# CH32L103G8R6-R0.net
KiCad netlist of a schematic drawn in Altium Designer
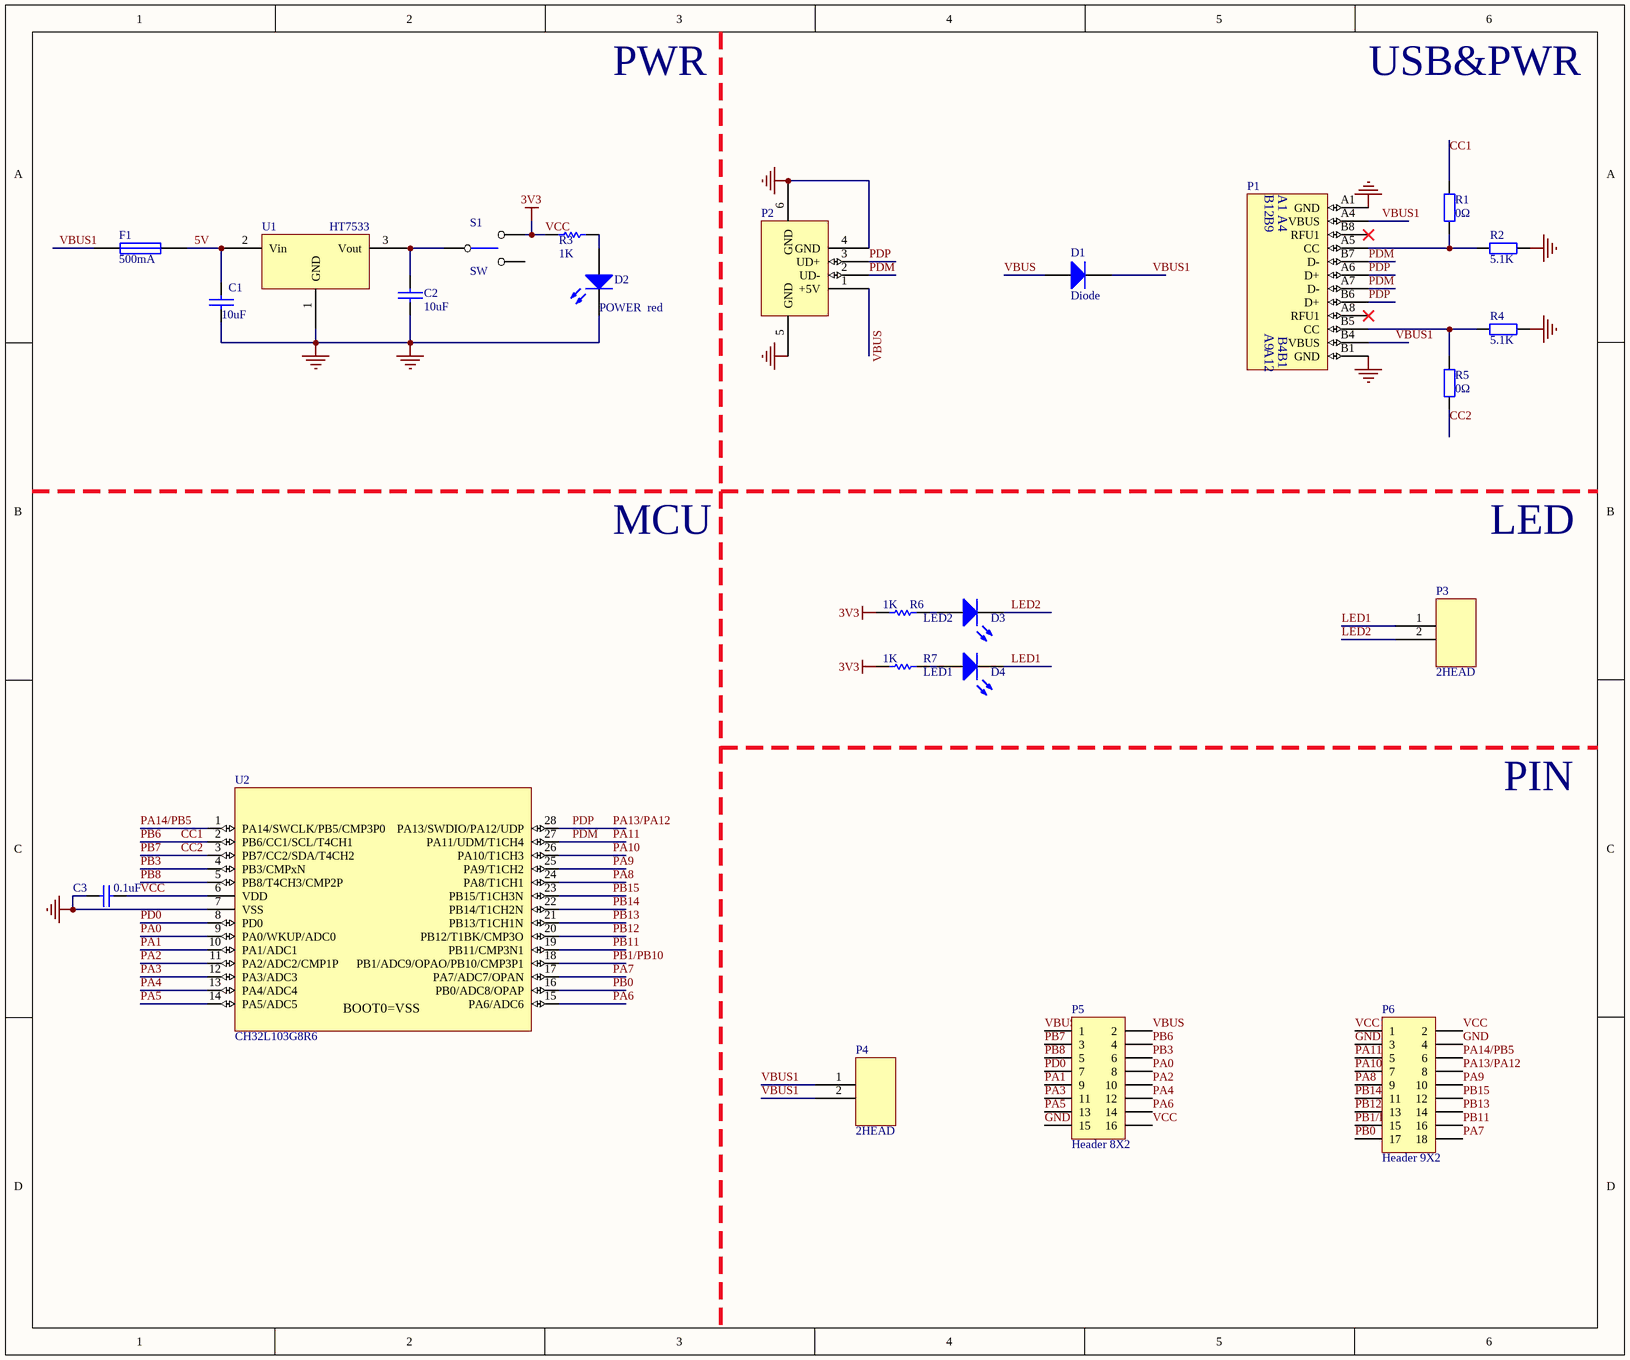
[diagram p0: CH32L103G8R6-R0.SchDoc]

(export (version "E")
  (design (tool "Eeschema 10.0.6"))
  (components
    (comp (ref "C1")
      (value "10uF")
      (footprint "0603_C")
      (description "Capacitor")
      (libsource (lib "*") (part "CAP"))
    )
    (comp (ref "C2")
      (value "10uF")
      (footprint "0603_C")
      (description "Capacitor")
      (libsource (lib "*") (part "CAP"))
    )
    (comp (ref "C3")
      (value "0.1uF")
      (footprint "0603_C")
      (description "Capacitor")
      (fields (field (name "PUBLISHER") "Altium Limited"))
      (libsource (lib "*") (part "Cap"))
    )
    (comp (ref "D1")
      (value "Diode")
      (footprint "SOD-123")
      (description "Default Diode")
      (fields (field (name "PUBLISHER") "Altium Limited"))
      (libsource (lib "Miscellaneous Devices") (part "Diode"))
    )
    (comp (ref "D2")
      (value "POWER  red")
      (footprint "0603+")
      (description "Typical INFRARED GaAs LED")
      (fields (field (name "PUBLISHER") "Altium Limited"))
      (libsource (lib "*") (part "LED0"))
    )
    (comp (ref "D3")
      (value "LED2")
      (footprint "0603+")
      (description "Typical INFRARED GaAs LED")
      (fields (field (name "PUBLISHER") "Altium Limited"))
      (libsource (lib "*") (part "LED0"))
    )
    (comp (ref "D4")
      (value "LED1")
      (footprint "0603+")
      (description "Typical INFRARED GaAs LED")
      (fields (field (name "PUBLISHER") "Altium Limited"))
      (libsource (lib "*") (part "LED0"))
    )
    (comp (ref "F1")
      (value "500mA")
      (footprint "0603")
      (description "Fuse")
      (libsource (lib "*") (part "FUSE1"))
    )
    (comp (ref "P1")
      (value "TYPE-C")
      (footprint "TYPE-C-Receptacle-2.0")
      (libsource (lib "*") (part "TYPE-C1"))
    )
    (comp (ref "P2")
      (value "USB_A")
      (footprint "USBAF")
      (description "USB Port")
      (libsource (lib "*") (part "USB"))
    )
    (comp (ref "P3") (value "2HEAD") (footprint "SIP2-2.54mm") (libsource (lib "*") (part "2HEAD")))
    (comp (ref "P4") (value "2HEAD") (footprint "SIP2-2.54mm") (libsource (lib "*") (part "2HEAD")))
    (comp (ref "P5")
      (value "Header 8X2")
      (footprint "HDR2X8")
      (description "Header, 8-Pin, Dual row")
      (fields (field (name "PUBLISHER") "Altium Limited"))
      (libsource (lib "Miscellaneous Connectors") (part "Header 8X2"))
    )
    (comp (ref "P6")
      (value "Header 9X2")
      (footprint "HDR2X9")
      (description "Header, 9-Pin, Dual row")
      (fields (field (name "PUBLISHER") "Altium Limited"))
      (libsource (lib "Miscellaneous Connectors") (part "Header 9X2"))
    )
    (comp (ref "R1")
      (value "0Ω")
      (footprint "0603")
      (description "Resistor")
      (libsource (lib "Miscellaneous Devices") (part "Res2"))
    )
    (comp (ref "R2")
      (value "5.1K")
      (footprint "0603")
      (description "Resistor")
      (libsource (lib "") (part "Res2_1"))
    )
    (comp (ref "R3")
      (value "1K")
      (footprint "0603")
      (description "Semiconductor Resistor")
      (libsource (lib "*") (part "Res Semi"))
    )
    (comp (ref "R4")
      (value "5.1K")
      (footprint "0603")
      (description "Resistor")
      (libsource (lib "") (part "Res2_1"))
    )
    (comp (ref "R5")
      (value "0Ω")
      (footprint "0603")
      (description "Resistor")
      (libsource (lib "Miscellaneous Devices") (part "Res2"))
    )
    (comp (ref "R6")
      (value "1K")
      (footprint "0603")
      (description "Semiconductor Resistor")
      (libsource (lib "*") (part "Res Semi"))
    )
    (comp (ref "R7")
      (value "1K")
      (footprint "0603")
      (description "Semiconductor Resistor")
      (libsource (lib "*") (part "Res Semi"))
    )
    (comp (ref "S1") (value "SW") (footprint "SW1") (libsource (lib "*") (part "SW")))
    (comp (ref "U1")
      (value "HT7533")
      (footprint "SOT-89")
      (libsource (lib "wch_sch_others") (part "1117-3.3V"))
    )
    (comp (ref "U2")
      (value "CH32L103G8R6")
      (footprint "QSOP28")
      (description "RISC-V LMD-MCU, 96MHz, USB, Type-C, CAN, OPA, lower power")
      (libsource (lib "DHXXXSCH") (part "CH32L103G8R6"))
    )
  )
  (nets
    (net (code "1") (name "/5V") (class "Default")
      (node (ref "C1") (pin "1") (pinfunction "1_1") (pintype "passive"))
      (node (ref "F1") (pin "2") (pinfunction "2_2") (pintype "passive"))
      (node (ref "U1") (pin "2") (pinfunction "Vin_2") (pintype "passive"))
    )
    (net (code "3") (name "/CC1") (class "Default")
      (node (ref "P5") (pin "4") (pinfunction "4_4") (pintype "passive"))
      (node (ref "R1") (pin "2") (pinfunction "2_2") (pintype "passive"))
      (node (ref "U2") (pin "2") (pinfunction "PB6/CC1/SCL/T4CH1_2") (pintype "bidirectional"))
    )
    (net (code "4") (name "/CC2") (class "Default")
      (node (ref "P5") (pin "3") (pinfunction "3_3") (pintype "passive"))
      (node (ref "R5") (pin "1") (pinfunction "1_1") (pintype "passive"))
      (node (ref "U2") (pin "3") (pinfunction "PB7/CC2/SDA/T4CH2_3") (pintype "bidirectional"))
    )
    (net (code "5") (name "/LED1") (class "Default")
      (node (ref "D4") (pin "2") (pinfunction "K_2") (pintype "passive"))
      (node (ref "P3") (pin "1") (pintype "passive"))
    )
    (net (code "6") (name "/LED2") (class "Default")
      (node (ref "D3") (pin "2") (pinfunction "K_2") (pintype "passive"))
      (node (ref "P3") (pin "2") (pintype "passive"))
    )
    (net (code "7") (name "/PA0") (class "Default")
      (node (ref "P5") (pin "8") (pinfunction "8_8") (pintype "passive"))
      (node (ref "U2") (pin "9") (pinfunction "PA0/WKUP/ADC0_9") (pintype "bidirectional"))
    )
    (net (code "8") (name "/PA1") (class "Default")
      (node (ref "P5") (pin "9") (pinfunction "9_9") (pintype "passive"))
      (node (ref "U2") (pin "10") (pinfunction "PA1/ADC1_10") (pintype "bidirectional"))
    )
    (net (code "9") (name "/PA2") (class "Default")
      (node (ref "P5") (pin "10") (pinfunction "10_10") (pintype "passive"))
      (node (ref "U2") (pin "11") (pinfunction "PA2/ADC2/CMP1P_11") (pintype "bidirectional"))
    )
    (net (code "10") (name "/PA3") (class "Default")
      (node (ref "P5") (pin "11") (pinfunction "11_11") (pintype "passive"))
      (node (ref "U2") (pin "12") (pinfunction "PA3/ADC3_12") (pintype "bidirectional"))
    )
    (net (code "11") (name "/PA4") (class "Default")
      (node (ref "P5") (pin "12") (pinfunction "12_12") (pintype "passive"))
      (node (ref "U2") (pin "13") (pinfunction "PA4/ADC4_13") (pintype "bidirectional"))
    )
    (net (code "12") (name "/PA5") (class "Default")
      (node (ref "P5") (pin "13") (pinfunction "13_13") (pintype "passive"))
      (node (ref "U2") (pin "14") (pinfunction "PA5/ADC5_14") (pintype "bidirectional"))
    )
    (net (code "13") (name "/PA6") (class "Default")
      (node (ref "P5") (pin "14") (pinfunction "14_14") (pintype "passive"))
      (node (ref "U2") (pin "15") (pinfunction "PA6/ADC6_15") (pintype "bidirectional"))
    )
    (net (code "14") (name "/PA7") (class "Default")
      (node (ref "P6") (pin "18") (pinfunction "18_18") (pintype "passive"))
      (node (ref "U2") (pin "17") (pinfunction "PA7/ADC7/OPAN_17") (pintype "bidirectional"))
    )
    (net (code "15") (name "/PA8") (class "Default")
      (node (ref "P6") (pin "9") (pinfunction "9_9") (pintype "passive"))
      (node (ref "U2") (pin "24") (pinfunction "PA8/T1CH1_24") (pintype "bidirectional"))
    )
    (net (code "16") (name "/PA9") (class "Default")
      (node (ref "P6") (pin "10") (pinfunction "10_10") (pintype "passive"))
      (node (ref "U2") (pin "25") (pinfunction "PA9/T1CH2_25") (pintype "bidirectional"))
    )
    (net (code "17") (name "/PA10") (class "Default")
      (node (ref "P6") (pin "7") (pinfunction "7_7") (pintype "passive"))
      (node (ref "U2") (pin "26") (pinfunction "PA10/T1CH3_26") (pintype "bidirectional"))
    )
    (net (code "18") (name "/PA11") (class "Default")
      (node (ref "P1") (pin "A7") (pinfunction "D-_A7") (pintype "bidirectional"))
      (node (ref "P1") (pin "B7") (pinfunction "D-_B7") (pintype "bidirectional"))
      (node (ref "P2") (pin "2") (pinfunction "UD-_2") (pintype "bidirectional"))
      (node (ref "P6") (pin "5") (pinfunction "5_5") (pintype "passive"))
      (node (ref "U2") (pin "27") (pinfunction "PA11/UDM/T1CH4_27") (pintype "bidirectional"))
    )
    (net (code "19") (name "/PA13{slash}PA12") (class "Default")
      (node (ref "P1") (pin "A6") (pinfunction "D+_A6") (pintype "bidirectional"))
      (node (ref "P1") (pin "B6") (pinfunction "D+_B6") (pintype "bidirectional"))
      (node (ref "P2") (pin "3") (pinfunction "UD+_3") (pintype "bidirectional"))
      (node (ref "P6") (pin "8") (pinfunction "8_8") (pintype "passive"))
      (node (ref "U2") (pin "28") (pinfunction "PA13/SWDIO/PA12/UDP_28") (pintype "bidirectional"))
    )
    (net (code "20") (name "/PA14{slash}PB5") (class "Default")
      (node (ref "P6") (pin "6") (pinfunction "6_6") (pintype "passive"))
      (node (ref "U2") (pin "1") (pinfunction "PA14/SWCLK/PB5/CMP3P0_1") (pintype "bidirectional"))
    )
    (net (code "21") (name "/PB0") (class "Default")
      (node (ref "P6") (pin "17") (pinfunction "17_17") (pintype "passive"))
      (node (ref "U2") (pin "16") (pinfunction "PB0/ADC8/OPAP_16") (pintype "bidirectional"))
    )
    (net (code "22") (name "/PB1{slash}PB10") (class "Default")
      (node (ref "P6") (pin "15") (pinfunction "15_15") (pintype "passive"))
      (node (ref "U2") (pin "18") (pinfunction "PB1/ADC9/OPAO/PB10/CMP3P1_18") (pintype "bidirectional"))
    )
    (net (code "23") (name "/PB3") (class "Default")
      (node (ref "P5") (pin "6") (pinfunction "6_6") (pintype "passive"))
      (node (ref "U2") (pin "4") (pinfunction "PB3/CMPxN_4") (pintype "bidirectional"))
    )
    (net (code "24") (name "/PB8") (class "Default")
      (node (ref "P5") (pin "5") (pinfunction "5_5") (pintype "passive"))
      (node (ref "U2") (pin "5") (pinfunction "PB8/T4CH3/CMP2P_5") (pintype "bidirectional"))
    )
    (net (code "25") (name "/PB11") (class "Default")
      (node (ref "P6") (pin "16") (pinfunction "16_16") (pintype "passive"))
      (node (ref "U2") (pin "19") (pinfunction "PB11/CMP3N1_19") (pintype "bidirectional"))
    )
    (net (code "26") (name "/PB12") (class "Default")
      (node (ref "P6") (pin "13") (pinfunction "13_13") (pintype "passive"))
      (node (ref "U2") (pin "20") (pinfunction "PB12/T1BK/CMP3O_20") (pintype "bidirectional"))
    )
    (net (code "27") (name "/PB13") (class "Default")
      (node (ref "P6") (pin "14") (pinfunction "14_14") (pintype "passive"))
      (node (ref "U2") (pin "21") (pinfunction "PB13/T1CH1N_21") (pintype "bidirectional"))
    )
    (net (code "28") (name "/PB14") (class "Default")
      (node (ref "P6") (pin "11") (pinfunction "11_11") (pintype "passive"))
      (node (ref "U2") (pin "22") (pinfunction "PB14/T1CH2N_22") (pintype "bidirectional"))
    )
    (net (code "29") (name "/PB15") (class "Default")
      (node (ref "P6") (pin "12") (pinfunction "12_12") (pintype "passive"))
      (node (ref "U2") (pin "23") (pinfunction "PB15/T1CH3N_23") (pintype "bidirectional"))
    )
    (net (code "30") (name "/PD0") (class "Default")
      (node (ref "P5") (pin "7") (pinfunction "7_7") (pintype "passive"))
      (node (ref "U2") (pin "8") (pinfunction "PD0_8") (pintype "bidirectional"))
    )
    (net (code "31") (name "/VBUS") (class "Default")
      (node (ref "D1") (pin "1") (pinfunction "A_1") (pintype "passive"))
      (node (ref "P2") (pin "1") (pinfunction "+5V_1") (pintype "power_in"))
      (node (ref "P5") (pin "1") (pinfunction "1_1") (pintype "passive"))
      (node (ref "P5") (pin "2") (pinfunction "2_2") (pintype "passive"))
    )
    (net (code "32") (name "/VBUS1") (class "Default")
      (node (ref "D1") (pin "2") (pinfunction "K_2") (pintype "passive"))
      (node (ref "F1") (pin "1") (pinfunction "1_1") (pintype "passive"))
      (node (ref "P1") (pin "A4") (pinfunction "VBUS_A4") (pintype "bidirectional"))
      (node (ref "P1") (pin "B4") (pinfunction "VBUS_B4") (pintype "bidirectional"))
      (node (ref "P4") (pin "1") (pintype "passive"))
      (node (ref "P4") (pin "2") (pintype "passive"))
    )
    (net (code "33") (name "3V3") (class "Default")
      (node (ref "C3") (pin "1") (pinfunction "1_1") (pintype "passive"))
      (node (ref "P5") (pin "16") (pinfunction "16_16") (pintype "passive"))
      (node (ref "P6") (pin "1") (pinfunction "1_1") (pintype "passive"))
      (node (ref "P6") (pin "2") (pinfunction "2_2") (pintype "passive"))
      (node (ref "R3") (pin "2") (pinfunction "2_2") (pintype "passive"))
      (node (ref "R6") (pin "1") (pinfunction "1_1") (pintype "passive"))
      (node (ref "R7") (pin "1") (pinfunction "1_1") (pintype "passive"))
      (node (ref "S1") (pin "3") (pinfunction "3_3") (pintype "passive"))
      (node (ref "U2") (pin "6") (pinfunction "VDD_6") (pintype "power_in"))
    )
    (net (code "34") (name "GND") (class "Default")
      (node (ref "C1") (pin "2") (pinfunction "2_2") (pintype "passive"))
      (node (ref "C2") (pin "2") (pinfunction "2_2") (pintype "passive"))
      (node (ref "C3") (pin "2") (pinfunction "2_2") (pintype "passive"))
      (node (ref "D2") (pin "2") (pinfunction "K_2") (pintype "passive"))
      (node (ref "P1") (pin "A1") (pinfunction "GND_A1") (pintype "bidirectional"))
      (node (ref "P1") (pin "B1") (pinfunction "GND_B1") (pintype "bidirectional"))
      (node (ref "P2") (pin "4") (pinfunction "GND_4") (pintype "power_in"))
      (node (ref "P2") (pin "5") (pinfunction "GND_5") (pintype "power_in"))
      (node (ref "P2") (pin "6") (pinfunction "GND_6") (pintype "power_in"))
      (node (ref "P5") (pin "15") (pinfunction "15_15") (pintype "passive"))
      (node (ref "P6") (pin "3") (pinfunction "3_3") (pintype "passive"))
      (node (ref "P6") (pin "4") (pinfunction "4_4") (pintype "passive"))
      (node (ref "R2") (pin "2") (pinfunction "2_2") (pintype "passive"))
      (node (ref "R4") (pin "2") (pinfunction "2_2") (pintype "passive"))
      (node (ref "U1") (pin "1") (pinfunction "GND_1") (pintype "passive"))
      (node (ref "U2") (pin "7") (pinfunction "VSS_7") (pintype "power_in"))
    )
    (net (code "35") (name "Net-(D2-A)") (class "Default")
      (node (ref "D2") (pin "1") (pinfunction "A_1") (pintype "passive"))
      (node (ref "R3") (pin "1") (pinfunction "1_1") (pintype "passive"))
    )
    (net (code "36") (name "Net-(D3-A)") (class "Default")
      (node (ref "D3") (pin "1") (pinfunction "A_1") (pintype "passive"))
      (node (ref "R6") (pin "2") (pinfunction "2_2") (pintype "passive"))
    )
    (net (code "37") (name "Net-(D4-A)") (class "Default")
      (node (ref "D4") (pin "1") (pinfunction "A_1") (pintype "passive"))
      (node (ref "R7") (pin "2") (pinfunction "2_2") (pintype "passive"))
    )
    (net (code "38") (name "Net-(P1-CC-PadA5)") (class "Default")
      (node (ref "P1") (pin "A5") (pinfunction "CC_A5") (pintype "bidirectional"))
      (node (ref "R1") (pin "1") (pinfunction "1_1") (pintype "passive"))
      (node (ref "R2") (pin "1") (pinfunction "1_1") (pintype "passive"))
    )
    (net (code "39") (name "Net-(P1-CC-PadB5)") (class "Default")
      (node (ref "P1") (pin "B5") (pinfunction "CC_B5") (pintype "bidirectional"))
      (node (ref "R4") (pin "1") (pinfunction "1_1") (pintype "passive"))
      (node (ref "R5") (pin "2") (pinfunction "2_2") (pintype "passive"))
    )
    (net (code "40") (name "Net-(U1-Vout)") (class "Default")
      (node (ref "C2") (pin "1") (pinfunction "1_1") (pintype "passive"))
      (node (ref "S1") (pin "1") (pinfunction "1_1") (pintype "passive"))
      (node (ref "U1") (pin "3") (pinfunction "Vout_3") (pintype "passive"))
    )
    (net (code "41") (name "unconnected-(P1-RFU1-PadA8)") (class "Default")
      (node (ref "P1") (pin "A8") (pinfunction "RFU1_A8") (pintype "bidirectional+no_connect"))
    )
    (net (code "42") (name "unconnected-(P1-RFU1-PadB8)") (class "Default")
      (node (ref "P1") (pin "B8") (pinfunction "RFU1_B8") (pintype "bidirectional+no_connect"))
    )
    (net (code "43") (name "unconnected-(S1-Pad2)") (class "Default")
      (node (ref "S1") (pin "2") (pinfunction "2_2") (pintype "passive"))
    )
  )
)
